# SINTETIZADOR_Y_DDS_SLAVE.net
KiCad netlist of a schematic drawn in Altium Designer
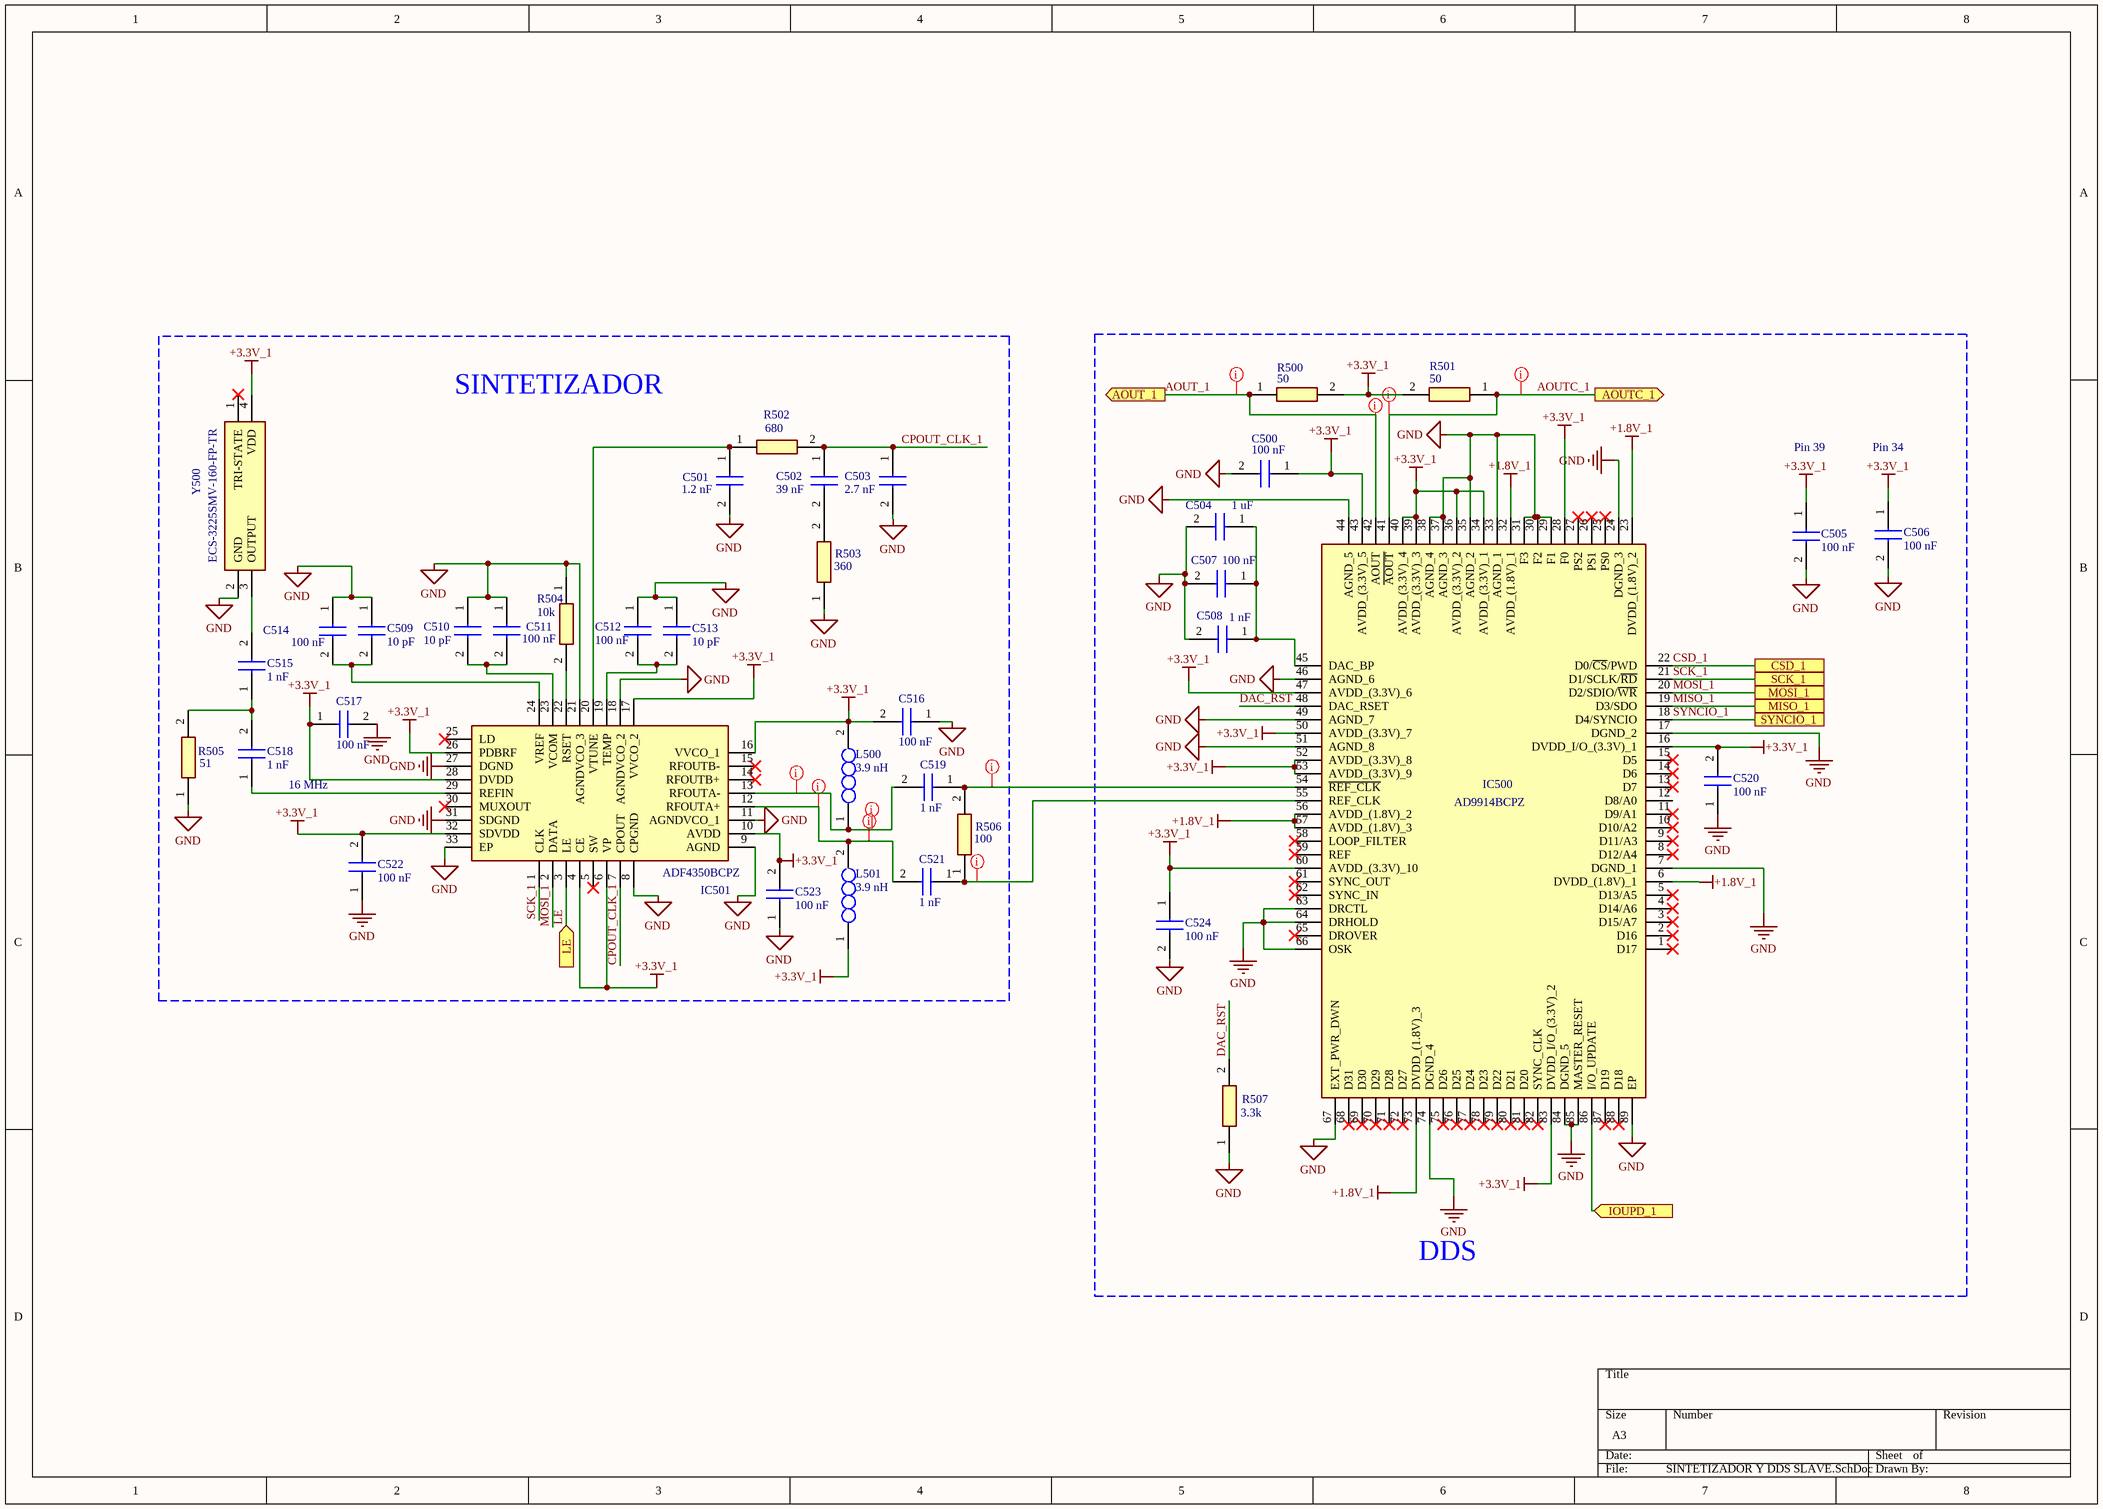
[diagram p0: SINTETIZADOR Y DDS SLAVE.SchDoc]

(export (version "E")
  (design (tool "Eeschema 10.0.6"))
  (components
    (comp (ref "C500")
      (value "100 nF")
      (footprint "SamacSys:C0603")
      (description "Capacitor")
      (fields (field (name "MANUFACTURER_PART_NUMBER") "C0603H470J5GACTU"))
      (libsource (lib "LIBRERIA_GEN_V2.0") (part "C0603H470J5GACTU"))
    )
    (comp (ref "C501")
      (value "1.2 nF")
      (footprint "SamacSys:C0603")
      (description "Capacitor")
      (fields (field (name "MANUFACTURER_PART_NUMBER") "C0603H470J5GACTU"))
      (libsource (lib "LIBRERIA_GEN_V2.0") (part "C0603H470J5GACTU"))
    )
    (comp (ref "C502")
      (value "39 nF")
      (footprint "SamacSys:C0603")
      (description "Capacitor")
      (fields (field (name "MANUFACTURER_PART_NUMBER") "C0603H470J5GACTU"))
      (libsource (lib "LIBRERIA_GEN_V2.0") (part "C0603H470J5GACTU"))
    )
    (comp (ref "C503")
      (value "2.7 nF")
      (footprint "SamacSys:C0603")
      (description "Capacitor")
      (fields (field (name "MANUFACTURER_PART_NUMBER") "C0603H470J5GACTU"))
      (libsource (lib "LIBRERIA_GEN_V2.0") (part "C0603H470J5GACTU"))
    )
    (comp (ref "C504")
      (value "1 uF")
      (footprint "SamacSys:C0603")
      (description "Capacitor")
      (fields (field (name "MANUFACTURER_PART_NUMBER") "C0603H470J5GACTU"))
      (libsource (lib "LIBRERIA_GEN_V2.0") (part "C0603H470J5GACTU"))
    )
    (comp (ref "C505")
      (value "100 nF")
      (footprint "SamacSys:C0603")
      (description "Capacitor")
      (fields (field (name "MANUFACTURER_PART_NUMBER") "C0603H470J5GACTU"))
      (libsource (lib "LIBRERIA_GEN_V2.0") (part "C0603H470J5GACTU"))
    )
    (comp (ref "C506")
      (value "100 nF")
      (footprint "SamacSys:C0603")
      (description "Capacitor")
      (fields (field (name "MANUFACTURER_PART_NUMBER") "C0603H470J5GACTU"))
      (libsource (lib "LIBRERIA_GEN_V2.0") (part "C0603H470J5GACTU"))
    )
    (comp (ref "C507")
      (value "100 nF")
      (footprint "SamacSys:C0603")
      (description "Capacitor")
      (fields (field (name "MANUFACTURER_PART_NUMBER") "C0603H470J5GACTU"))
      (libsource (lib "LIBRERIA_GEN_V2.0") (part "C0603H470J5GACTU"))
    )
    (comp (ref "C508")
      (value "1 nF")
      (footprint "SamacSys:C0603")
      (description "Capacitor")
      (fields (field (name "MANUFACTURER_PART_NUMBER") "C0603H470J5GACTU"))
      (libsource (lib "LIBRERIA_GEN_V2.0") (part "C0603H470J5GACTU"))
    )
    (comp (ref "C509")
      (value "10 pF")
      (footprint "SamacSys:C0603")
      (description "Capacitor")
      (fields (field (name "MANUFACTURER_PART_NUMBER") "C0603H470J5GACTU"))
      (libsource (lib "LIBRERIA_GEN_V2.0") (part "C0603H470J5GACTU"))
    )
    (comp (ref "C510")
      (value "10 pF")
      (footprint "SamacSys:C0603")
      (description "Capacitor")
      (fields (field (name "MANUFACTURER_PART_NUMBER") "C0603H470J5GACTU"))
      (libsource (lib "LIBRERIA_GEN_V2.0") (part "C0603H470J5GACTU"))
    )
    (comp (ref "C511")
      (value "100 nF")
      (footprint "SamacSys:C0603")
      (description "Capacitor")
      (fields (field (name "MANUFACTURER_PART_NUMBER") "C0603H470J5GACTU"))
      (libsource (lib "LIBRERIA_GEN_V2.0") (part "C0603H470J5GACTU"))
    )
    (comp (ref "C512")
      (value "100 nF")
      (footprint "SamacSys:C0603")
      (description "Capacitor")
      (fields (field (name "MANUFACTURER_PART_NUMBER") "C0603H470J5GACTU"))
      (libsource (lib "LIBRERIA_GEN_V2.0") (part "C0603H470J5GACTU"))
    )
    (comp (ref "C513")
      (value "10 pF")
      (footprint "SamacSys:C0603")
      (description "Capacitor")
      (fields (field (name "MANUFACTURER_PART_NUMBER") "C0603H470J5GACTU"))
      (libsource (lib "LIBRERIA_GEN_V2.0") (part "C0603H470J5GACTU"))
    )
    (comp (ref "C514")
      (value "100 nF")
      (footprint "SamacSys:C0603")
      (description "Capacitor")
      (fields (field (name "MANUFACTURER_PART_NUMBER") "C0603H470J5GACTU"))
      (libsource (lib "LIBRERIA_GEN_V2.0") (part "C0603H470J5GACTU"))
    )
    (comp (ref "C515")
      (value "1 nF")
      (footprint "SamacSys:C0603")
      (description "Capacitor")
      (fields (field (name "MANUFACTURER_PART_NUMBER") "C0603H470J5GACTU"))
      (libsource (lib "LIBRERIA_GEN_V2.0") (part "C0603H470J5GACTU"))
    )
    (comp (ref "C516")
      (value "100 nF")
      (footprint "SamacSys:C0603")
      (description "Capacitor")
      (fields (field (name "MANUFACTURER_PART_NUMBER") "C0603H470J5GACTU"))
      (libsource (lib "LIBRERIA_GEN_V2.0") (part "C0603H470J5GACTU"))
    )
    (comp (ref "C517")
      (value "100 nF")
      (footprint "SamacSys:C0603")
      (description "Capacitor")
      (fields (field (name "MANUFACTURER_PART_NUMBER") "C0603H470J5GACTU"))
      (libsource (lib "LIBRERIA_GEN_V2.0") (part "C0603H470J5GACTU"))
    )
    (comp (ref "C518")
      (value "1 nF")
      (footprint "SamacSys:C0603")
      (description "Capacitor")
      (fields (field (name "MANUFACTURER_PART_NUMBER") "C0603H470J5GACTU"))
      (libsource (lib "LIBRERIA_GEN_V2.0") (part "C0603H470J5GACTU"))
    )
    (comp (ref "C519")
      (value "1 nF")
      (footprint "SamacSys:C0603")
      (description "Capacitor")
      (fields (field (name "MANUFACTURER_PART_NUMBER") "C0603H470J5GACTU"))
      (libsource (lib "LIBRERIA_GEN_V2.0") (part "C0603H470J5GACTU"))
    )
    (comp (ref "C520")
      (value "100 nF")
      (footprint "SamacSys:C0603")
      (description "Capacitor")
      (fields (field (name "MANUFACTURER_PART_NUMBER") "C0603H470J5GACTU"))
      (libsource (lib "LIBRERIA_GEN_V2.0") (part "C0603H470J5GACTU"))
    )
    (comp (ref "C521")
      (value "1 nF")
      (footprint "SamacSys:C0603")
      (description "Capacitor")
      (fields (field (name "MANUFACTURER_PART_NUMBER") "C0603H470J5GACTU"))
      (libsource (lib "LIBRERIA_GEN_V2.0") (part "C0603H470J5GACTU"))
    )
    (comp (ref "C522")
      (value "100 nF")
      (footprint "SamacSys:C0603")
      (description "Capacitor")
      (fields (field (name "MANUFACTURER_PART_NUMBER") "C0603H470J5GACTU"))
      (libsource (lib "LIBRERIA_GEN_V2.0") (part "C0603H470J5GACTU"))
    )
    (comp (ref "C523")
      (value "100 nF")
      (footprint "SamacSys:C0603")
      (description "Capacitor")
      (fields (field (name "MANUFACTURER_PART_NUMBER") "C0603H470J5GACTU"))
      (libsource (lib "LIBRERIA_GEN_V2.0") (part "C0603H470J5GACTU"))
    )
    (comp (ref "C524")
      (value "100 nF")
      (footprint "SamacSys:C0603")
      (description "Capacitor")
      (fields (field (name "MANUFACTURER_PART_NUMBER") "C0603H470J5GACTU"))
      (libsource (lib "LIBRERIA_GEN_V2.0") (part "C0603H470J5GACTU"))
    )
    (comp (ref "IC500")
      (value "AD9914BCPZ")
      (footprint "SamacSys:QFN50P1200X1200X90-89N-D")
      (description "Integrated Circuit")
      (fields (field (name "MOUSER PART NUMBER") "584-AD9914BCPZ"))
      (libsource (lib "LIBRERIA_GEN_V2.0") (part "AD9914BCPZ"))
    )
    (comp (ref "IC501")
      (value "ADF4350BCPZ")
      (footprint "SamacSys:QFN50P500X500X100-33N")
      (description "Integrated Circuit")
      (fields (field (name "MOUSER PART NUMBER") "584-ADF4350BCPZ"))
      (libsource (lib "LIBRERIA_GEN_V2.0") (part "ADF4350BCPZ"))
    )
    (comp (ref "L500")
      (value "3.9 nH")
      (footprint "SamacSys:INDC1608X95N")
      (description "Inductor")
      (fields
        (field (name "MANUFACTURER_PART_NUMBER") "AIML-0603-100K-T")
        (field (name "MOUSER PART NUMBER") "815-AIML-0603-100KT")
      )
      (libsource (lib "*") (part "AIML-0603-100K-T"))
    )
    (comp (ref "L501")
      (value "3.9 nH")
      (footprint "SamacSys:INDC1608X95N")
      (description "Inductor")
      (fields
        (field (name "MANUFACTURER_PART_NUMBER") "AIML-0603-100K-T")
        (field (name "MOUSER PART NUMBER") "815-AIML-0603-100KT")
      )
      (libsource (lib "*") (part "AIML-0603-100K-T"))
    )
    (comp (ref "R500")
      (value "50")
      (footprint "SamacSys:RESC1608X55N")
      (description "Resistor")
      (fields
        (field (name "MANUFACTURER_PART_NUMBER") "CR0603-FX-1431ELF")
        (field (name "MOUSER PART NUMBER") "652-CR0603FX-1431ELF")
      )
      (libsource (lib "") (part "CR0603-FX-1431ELF_1"))
    )
    (comp (ref "R501")
      (value "50")
      (footprint "SamacSys:RESC1608X55N")
      (description "Resistor")
      (fields
        (field (name "MANUFACTURER_PART_NUMBER") "CR0603-FX-1431ELF")
        (field (name "MOUSER PART NUMBER") "652-CR0603FX-1431ELF")
      )
      (libsource (lib "") (part "CR0603-FX-1431ELF_2"))
    )
    (comp (ref "R502")
      (value "680")
      (footprint "SamacSys:RESC1608X55N")
      (description "Resistor")
      (fields
        (field (name "MANUFACTURER_PART_NUMBER") "CR0603-FX-1431ELF")
        (field (name "MOUSER PART NUMBER") "652-CR0603FX-1431ELF")
      )
      (libsource (lib "") (part "CR0603-FX-1431ELF_1"))
    )
    (comp (ref "R503")
      (value "360")
      (footprint "SamacSys:RESC1608X55N")
      (description "Resistor")
      (fields
        (field (name "MANUFACTURER_PART_NUMBER") "CR0603-FX-1431ELF")
        (field (name "MOUSER PART NUMBER") "652-CR0603FX-1431ELF")
      )
      (libsource (lib "") (part "CR0603-FX-1431ELF_3"))
    )
    (comp (ref "R504")
      (value "10k")
      (footprint "SamacSys:RESC1608X55N")
      (description "Resistor")
      (fields
        (field (name "MANUFACTURER_PART_NUMBER") "CR0603-FX-1431ELF")
        (field (name "MOUSER PART NUMBER") "652-CR0603FX-1431ELF")
      )
      (libsource (lib "LIBRERIA_GEN_V2.0") (part "CR0603-FX-1431ELF"))
    )
    (comp (ref "R505")
      (value "51")
      (footprint "SamacSys:RESC1608X55N")
      (description "Resistor")
      (fields
        (field (name "MANUFACTURER_PART_NUMBER") "CR0603-FX-1431ELF")
        (field (name "MOUSER PART NUMBER") "652-CR0603FX-1431ELF")
      )
      (libsource (lib "") (part "CR0603-FX-1431ELF_3"))
    )
    (comp (ref "R506")
      (value "100")
      (footprint "SamacSys:RESC1608X55N")
      (description "Resistor")
      (fields
        (field (name "MANUFACTURER_PART_NUMBER") "CR0603-FX-1431ELF")
        (field (name "MOUSER PART NUMBER") "652-CR0603FX-1431ELF")
      )
      (libsource (lib "") (part "CR0603-FX-1431ELF_3"))
    )
    (comp (ref "R507")
      (value "3.3k")
      (footprint "SamacSys:RESC1608X55N")
      (description "Resistor")
      (fields
        (field (name "MANUFACTURER_PART_NUMBER") "CR0603-FX-1431ELF")
        (field (name "MOUSER PART NUMBER") "652-CR0603FX-1431ELF")
      )
      (libsource (lib "") (part "CR0603-FX-1431ELF_3"))
    )
    (comp (ref "Y500")
      (value "ECS-3225SMV-160-FP-TR")
      (footprint "SamacSys:ECS3225SMV160FPTR")
      (description "Crystal or Oscillator")
      (fields (field (name "MOUSER PART NUMBER") "520-3225SMV-160-FPT"))
      (libsource (lib "LIBRERIA_GEN_V2.0") (part "ECS-3225SMV-160-FP-TR"))
    )
  )
  (nets
    (net (code "1") (name "+1.8V_1") (class "Default")
      (node (ref "IC500") (pin "23") (pinfunction "DVDD_(1.8V)_2_23") (pintype "passive"))
      (node (ref "IC500") (pin "32") (pinfunction "AVDD_(1.8V)_1_32") (pintype "passive"))
      (node (ref "IC500") (pin "56") (pinfunction "AVDD_(1.8V)_2_56") (pintype "passive"))
      (node (ref "IC500") (pin "57") (pinfunction "AVDD_(1.8V)_3_57") (pintype "passive"))
      (node (ref "IC500") (pin "6") (pinfunction "DVDD_(1.8V)_1_6") (pintype "passive"))
      (node (ref "IC500") (pin "73") (pinfunction "DVDD_(1.8V)_3_73") (pintype "passive"))
    )
    (net (code "2") (name "+3.3V_1") (class "Default")
      (node (ref "C500") (pin "1") (pinfunction "1_1") (pintype "passive"))
      (node (ref "C505") (pin "1") (pinfunction "1_1") (pintype "passive"))
      (node (ref "C506") (pin "1") (pinfunction "1_1") (pintype "passive"))
      (node (ref "C516") (pin "2") (pinfunction "2_2") (pintype "passive"))
      (node (ref "C517") (pin "1") (pinfunction "1_1") (pintype "passive"))
      (node (ref "C520") (pin "2") (pinfunction "2_2") (pintype "passive"))
      (node (ref "C522") (pin "2") (pinfunction "2_2") (pintype "passive"))
      (node (ref "C523") (pin "2") (pinfunction "2_2") (pintype "passive"))
      (node (ref "C524") (pin "1") (pinfunction "1_1") (pintype "passive"))
      (node (ref "IC500") (pin "16") (pinfunction "DVDD_I/O_(3.3V)_1_16") (pintype "passive"))
      (node (ref "IC500") (pin "28") (pinfunction "F0_28") (pintype "passive"))
      (node (ref "IC500") (pin "34") (pinfunction "AVDD_(3.3V)_1_34") (pintype "passive"))
      (node (ref "IC500") (pin "36") (pinfunction "AVDD_(3.3V)_2_36") (pintype "passive"))
      (node (ref "IC500") (pin "39") (pinfunction "AVDD_(3.3V)_3_39") (pintype "passive"))
      (node (ref "IC500") (pin "40") (pinfunction "AVDD_(3.3V)_4_40") (pintype "passive"))
      (node (ref "IC500") (pin "43") (pinfunction "AVDD_(3.3V)_5_43") (pintype "passive"))
      (node (ref "IC500") (pin "47") (pinfunction "AVDD_(3.3V)_6_47") (pintype "passive"))
      (node (ref "IC500") (pin "50") (pinfunction "AVDD_(3.3V)_7_50") (pintype "passive"))
      (node (ref "IC500") (pin "52") (pinfunction "AVDD_(3.3V)_8_52") (pintype "passive"))
      (node (ref "IC500") (pin "53") (pinfunction "AVDD_(3.3V)_9_53") (pintype "passive"))
      (node (ref "IC500") (pin "60") (pinfunction "AVDD_(3.3V)_10_60") (pintype "passive"))
      (node (ref "IC500") (pin "83") (pinfunction "DVDD_I/O_(3.3V)_2_83") (pintype "passive"))
      (node (ref "IC501") (pin "10") (pinfunction "AVDD_10") (pintype "passive"))
      (node (ref "IC501") (pin "16") (pinfunction "VVCO_1_16") (pintype "passive"))
      (node (ref "IC501") (pin "17") (pinfunction "VVCO_2_17") (pintype "passive"))
      (node (ref "IC501") (pin "26") (pinfunction "PDBRF_26") (pintype "passive"))
      (node (ref "IC501") (pin "28") (pinfunction "DVDD_28") (pintype "passive"))
      (node (ref "IC501") (pin "32") (pinfunction "SDVDD_32") (pintype "passive"))
      (node (ref "IC501") (pin "4") (pinfunction "CE_4") (pintype "passive"))
      (node (ref "IC501") (pin "6") (pinfunction "VP_6") (pintype "passive"))
      (node (ref "L500") (pin "2") (pinfunction "2_2") (pintype "passive"))
      (node (ref "L501") (pin "1") (pinfunction "1_1") (pintype "passive"))
      (node (ref "R500") (pin "2") (pinfunction "2_2") (pintype "passive"))
      (node (ref "R501") (pin "2") (pinfunction "2_2") (pintype "passive"))
      (node (ref "Y500") (pin "4") (pinfunction "VDD_4") (pintype "passive"))
    )
    (net (code "3") (name "/AOUTC_1") (class "Default")
      (node (ref "IC500") (pin "41") (pinfunction "~{AOUT}_41") (pintype "passive"))
      (node (ref "R501") (pin "1") (pinfunction "1_1") (pintype "passive"))
    )
    (net (code "4") (name "/AOUT_1") (class "Default")
      (node (ref "IC500") (pin "42") (pinfunction "AOUT_42") (pintype "passive"))
      (node (ref "R500") (pin "1") (pinfunction "1_1") (pintype "passive"))
    )
    (net (code "5") (name "/CPOUT_CLK_1") (class "Default")
      (node (ref "C502") (pin "1") (pinfunction "1_1") (pintype "passive"))
      (node (ref "C503") (pin "1") (pinfunction "1_1") (pintype "passive"))
      (node (ref "IC501") (pin "7") (pinfunction "CPOUT_7") (pintype "passive"))
      (node (ref "R502") (pin "2") (pinfunction "2_2") (pintype "passive"))
    )
    (net (code "6") (name "/CSD_1") (class "Default")
      (node (ref "IC500") (pin "22") (pinfunction "D0/~{CS}/PWD_22") (pintype "passive"))
    )
    (net (code "7") (name "/DAC_RST") (class "Default")
      (node (ref "IC500") (pin "48") (pinfunction "DAC_RSET_48") (pintype "passive"))
      (node (ref "R507") (pin "2") (pinfunction "2_2") (pintype "passive"))
    )
    (net (code "8") (name "/IOUPD_1") (class "Default")
      (node (ref "IC500") (pin "86") (pinfunction "I/O_UPDATE_86") (pintype "passive"))
    )
    (net (code "9") (name "/LE") (class "Default")
      (node (ref "IC501") (pin "3") (pinfunction "LE_3") (pintype "passive"))
    )
    (net (code "10") (name "/MISO_1") (class "Default")
      (node (ref "IC500") (pin "19") (pinfunction "D3/SDO_19") (pintype "passive"))
    )
    (net (code "11") (name "/MOSI_1") (class "Default")
      (node (ref "IC500") (pin "20") (pinfunction "D2/SDIO/~{WR}_20") (pintype "passive"))
      (node (ref "IC501") (pin "2") (pinfunction "DATA_2") (pintype "passive"))
    )
    (net (code "12") (name "/SCK_1") (class "Default")
      (node (ref "IC500") (pin "21") (pinfunction "D1/SCLK/~{RD}_21") (pintype "passive"))
      (node (ref "IC501") (pin "1") (pinfunction "CLK_1") (pintype "passive"))
    )
    (net (code "13") (name "/SYNCIO_1") (class "Default")
      (node (ref "IC500") (pin "18") (pinfunction "D4/SYNCIO_18") (pintype "passive"))
    )
    (net (code "14") (name "GND") (class "Default")
      (node (ref "C500") (pin "2") (pinfunction "2_2") (pintype "passive"))
      (node (ref "C501") (pin "2") (pinfunction "2_2") (pintype "passive"))
      (node (ref "C503") (pin "2") (pinfunction "2_2") (pintype "passive"))
      (node (ref "C504") (pin "2") (pinfunction "2_2") (pintype "passive"))
      (node (ref "C505") (pin "2") (pinfunction "2_2") (pintype "passive"))
      (node (ref "C506") (pin "2") (pinfunction "2_2") (pintype "passive"))
      (node (ref "C507") (pin "2") (pinfunction "2_2") (pintype "passive"))
      (node (ref "C508") (pin "2") (pinfunction "2_2") (pintype "passive"))
      (node (ref "C509") (pin "1") (pinfunction "1_1") (pintype "passive"))
      (node (ref "C510") (pin "1") (pinfunction "1_1") (pintype "passive"))
      (node (ref "C511") (pin "1") (pinfunction "1_1") (pintype "passive"))
      (node (ref "C512") (pin "1") (pinfunction "1_1") (pintype "passive"))
      (node (ref "C513") (pin "1") (pinfunction "1_1") (pintype "passive"))
      (node (ref "C514") (pin "1") (pinfunction "1_1") (pintype "passive"))
      (node (ref "C516") (pin "1") (pinfunction "1_1") (pintype "passive"))
      (node (ref "C517") (pin "2") (pinfunction "2_2") (pintype "passive"))
      (node (ref "C520") (pin "1") (pinfunction "1_1") (pintype "passive"))
      (node (ref "C522") (pin "1") (pinfunction "1_1") (pintype "passive"))
      (node (ref "C523") (pin "1") (pinfunction "1_1") (pintype "passive"))
      (node (ref "C524") (pin "2") (pinfunction "2_2") (pintype "passive"))
      (node (ref "IC500") (pin "17") (pinfunction "DGND_2_17") (pintype "passive"))
      (node (ref "IC500") (pin "24") (pinfunction "DGND_3_24") (pintype "passive"))
      (node (ref "IC500") (pin "29") (pinfunction "F1_29") (pintype "passive"))
      (node (ref "IC500") (pin "30") (pinfunction "F2_30") (pintype "passive"))
      (node (ref "IC500") (pin "31") (pinfunction "F3_31") (pintype "passive"))
      (node (ref "IC500") (pin "33") (pinfunction "AGND_1_33") (pintype "passive"))
      (node (ref "IC500") (pin "35") (pinfunction "AGND_2_35") (pintype "passive"))
      (node (ref "IC500") (pin "37") (pinfunction "AGND_3_37") (pintype "passive"))
      (node (ref "IC500") (pin "38") (pinfunction "AGND_4_38") (pintype "passive"))
      (node (ref "IC500") (pin "44") (pinfunction "AGND_5_44") (pintype "passive"))
      (node (ref "IC500") (pin "46") (pinfunction "AGND_6_46") (pintype "passive"))
      (node (ref "IC500") (pin "49") (pinfunction "AGND_7_49") (pintype "passive"))
      (node (ref "IC500") (pin "51") (pinfunction "AGND_8_51") (pintype "passive"))
      (node (ref "IC500") (pin "63") (pinfunction "DRCTL_63") (pintype "passive"))
      (node (ref "IC500") (pin "64") (pinfunction "DRHOLD_64") (pintype "passive"))
      (node (ref "IC500") (pin "66") (pinfunction "OSK_66") (pintype "passive"))
      (node (ref "IC500") (pin "67") (pinfunction "EXT_PWR_DWN_67") (pintype "passive"))
      (node (ref "IC500") (pin "7") (pinfunction "DGND_1_7") (pintype "passive"))
      (node (ref "IC500") (pin "74") (pinfunction "DGND_4_74") (pintype "passive"))
      (node (ref "IC500") (pin "84") (pinfunction "DGND_5_84") (pintype "passive"))
      (node (ref "IC500") (pin "85") (pinfunction "MASTER_RESET_85") (pintype "passive"))
      (node (ref "IC500") (pin "89") (pinfunction "EP_89") (pintype "passive"))
      (node (ref "IC501") (pin "11") (pinfunction "AGNDVCO_1_11") (pintype "passive"))
      (node (ref "IC501") (pin "18") (pinfunction "AGNDVCO_2_18") (pintype "passive"))
      (node (ref "IC501") (pin "21") (pinfunction "AGNDVCO_3_21") (pintype "passive"))
      (node (ref "IC501") (pin "27") (pinfunction "DGND_27") (pintype "passive"))
      (node (ref "IC501") (pin "31") (pinfunction "SDGND_31") (pintype "passive"))
      (node (ref "IC501") (pin "33") (pinfunction "EP_33") (pintype "passive"))
      (node (ref "IC501") (pin "8") (pinfunction "CPGND_8") (pintype "passive"))
      (node (ref "IC501") (pin "9") (pinfunction "AGND_9") (pintype "passive"))
      (node (ref "R503") (pin "1") (pinfunction "1_1") (pintype "passive"))
      (node (ref "R504") (pin "1") (pinfunction "1_1") (pintype "passive"))
      (node (ref "R505") (pin "1") (pinfunction "1_1") (pintype "passive"))
      (node (ref "R507") (pin "1") (pinfunction "1_1") (pintype "passive"))
      (node (ref "Y500") (pin "2") (pinfunction "GND_2") (pintype "passive"))
    )
    (net (code "15") (name "Net-(C502-Pad2)") (class "Default")
      (node (ref "C502") (pin "2") (pinfunction "2_2") (pintype "passive"))
      (node (ref "R503") (pin "2") (pinfunction "2_2") (pintype "passive"))
    )
    (net (code "16") (name "Net-(C515-Pad1)") (class "Default")
      (node (ref "C515") (pin "1") (pinfunction "1_1") (pintype "passive"))
      (node (ref "C518") (pin "2") (pinfunction "2_2") (pintype "passive"))
      (node (ref "R505") (pin "2") (pinfunction "2_2") (pintype "passive"))
    )
    (net (code "17") (name "Net-(IC500-DAC_BP)") (class "Default")
      (node (ref "C504") (pin "1") (pinfunction "1_1") (pintype "passive"))
      (node (ref "C507") (pin "1") (pinfunction "1_1") (pintype "passive"))
      (node (ref "C508") (pin "1") (pinfunction "1_1") (pintype "passive"))
      (node (ref "IC500") (pin "45") (pinfunction "DAC_BP_45") (pintype "passive"))
    )
    (net (code "18") (name "Net-(IC500-REF_CLK)") (class "Default")
      (node (ref "C521") (pin "1") (pinfunction "1_1") (pintype "passive"))
      (node (ref "IC500") (pin "55") (pinfunction "REF_CLK_55") (pintype "passive"))
      (node (ref "R506") (pin "1") (pinfunction "1_1") (pintype "passive"))
    )
    (net (code "19") (name "Net-(IC500-~{REF_CLK})") (class "Default")
      (node (ref "C519") (pin "1") (pinfunction "1_1") (pintype "passive"))
      (node (ref "IC500") (pin "54") (pinfunction "~{REF_CLK}_54") (pintype "passive"))
      (node (ref "R506") (pin "2") (pinfunction "2_2") (pintype "passive"))
    )
    (net (code "20") (name "Net-(IC501-REFIN)") (class "Default")
      (node (ref "C518") (pin "1") (pinfunction "1_1") (pintype "passive"))
      (node (ref "IC501") (pin "29") (pinfunction "REFIN_29") (pintype "passive"))
    )
    (net (code "21") (name "Net-(IC501-RFOUTA+)") (class "Default")
      (node (ref "C521") (pin "2") (pinfunction "2_2") (pintype "passive"))
      (node (ref "IC501") (pin "12") (pinfunction "RFOUTA+_12") (pintype "passive"))
      (node (ref "L501") (pin "2") (pinfunction "2_2") (pintype "passive"))
    )
    (net (code "22") (name "Net-(IC501-RFOUTA-)") (class "Default")
      (node (ref "C519") (pin "2") (pinfunction "2_2") (pintype "passive"))
      (node (ref "IC501") (pin "13") (pinfunction "RFOUTA-_13") (pintype "passive"))
      (node (ref "L500") (pin "1") (pinfunction "1_1") (pintype "passive"))
    )
    (net (code "23") (name "Net-(IC501-RSET)") (class "Default")
      (node (ref "IC501") (pin "22") (pinfunction "RSET_22") (pintype "passive"))
      (node (ref "R504") (pin "2") (pinfunction "2_2") (pintype "passive"))
    )
    (net (code "24") (name "Net-(IC501-TEMP)") (class "Default")
      (node (ref "C512") (pin "2") (pinfunction "2_2") (pintype "passive"))
      (node (ref "C513") (pin "2") (pinfunction "2_2") (pintype "passive"))
      (node (ref "IC501") (pin "19") (pinfunction "TEMP_19") (pintype "passive"))
    )
    (net (code "25") (name "Net-(IC501-VCOM)") (class "Default")
      (node (ref "C510") (pin "2") (pinfunction "2_2") (pintype "passive"))
      (node (ref "C511") (pin "2") (pinfunction "2_2") (pintype "passive"))
      (node (ref "IC501") (pin "23") (pinfunction "VCOM_23") (pintype "passive"))
    )
    (net (code "26") (name "Net-(IC501-VREF)") (class "Default")
      (node (ref "C509") (pin "2") (pinfunction "2_2") (pintype "passive"))
      (node (ref "C514") (pin "2") (pinfunction "2_2") (pintype "passive"))
      (node (ref "IC501") (pin "24") (pinfunction "VREF_24") (pintype "passive"))
    )
    (net (code "27") (name "Net-(IC501-VTUNE)") (class "Default")
      (node (ref "C501") (pin "1") (pinfunction "1_1") (pintype "passive"))
      (node (ref "IC501") (pin "20") (pinfunction "VTUNE_20") (pintype "passive"))
      (node (ref "R502") (pin "1") (pinfunction "1_1") (pintype "passive"))
    )
    (net (code "28") (name "Net-(Y500-OUTPUT)") (class "Default")
      (node (ref "C515") (pin "2") (pinfunction "2_2") (pintype "passive"))
      (node (ref "Y500") (pin "3") (pinfunction "OUTPUT_3") (pintype "passive"))
    )
    (net (code "29") (name "unconnected-(IC500-D5-Pad15)") (class "Default")
      (node (ref "IC500") (pin "15") (pinfunction "D5_15") (pintype "passive+no_connect"))
    )
    (net (code "30") (name "unconnected-(IC500-D6-Pad14)") (class "Default")
      (node (ref "IC500") (pin "14") (pinfunction "D6_14") (pintype "passive+no_connect"))
    )
    (net (code "31") (name "unconnected-(IC500-D7-Pad13)") (class "Default")
      (node (ref "IC500") (pin "13") (pinfunction "D7_13") (pintype "passive+no_connect"))
    )
    (net (code "32") (name "unconnected-(IC500-D8{slash}A0-Pad12)") (class "Default")
      (node (ref "IC500") (pin "12") (pinfunction "D8/A0_12") (pintype "passive"))
    )
    (net (code "33") (name "unconnected-(IC500-D9{slash}A1-Pad11)") (class "Default")
      (node (ref "IC500") (pin "11") (pinfunction "D9/A1_11") (pintype "passive+no_connect"))
    )
    (net (code "34") (name "unconnected-(IC500-D10{slash}A2-Pad10)") (class "Default")
      (node (ref "IC500") (pin "10") (pinfunction "D10/A2_10") (pintype "passive+no_connect"))
    )
    (net (code "35") (name "unconnected-(IC500-D11{slash}A3-Pad9)") (class "Default")
      (node (ref "IC500") (pin "9") (pinfunction "D11/A3_9") (pintype "passive+no_connect"))
    )
    (net (code "36") (name "unconnected-(IC500-D12{slash}A4-Pad8)") (class "Default")
      (node (ref "IC500") (pin "8") (pinfunction "D12/A4_8") (pintype "passive+no_connect"))
    )
    (net (code "37") (name "unconnected-(IC500-D13{slash}A5-Pad5)") (class "Default")
      (node (ref "IC500") (pin "5") (pinfunction "D13/A5_5") (pintype "passive+no_connect"))
    )
    (net (code "38") (name "unconnected-(IC500-D14{slash}A6-Pad4)") (class "Default")
      (node (ref "IC500") (pin "4") (pinfunction "D14/A6_4") (pintype "passive+no_connect"))
    )
    (net (code "39") (name "unconnected-(IC500-D15{slash}A7-Pad3)") (class "Default")
      (node (ref "IC500") (pin "3") (pinfunction "D15/A7_3") (pintype "passive+no_connect"))
    )
    (net (code "40") (name "unconnected-(IC500-D16-Pad2)") (class "Default")
      (node (ref "IC500") (pin "2") (pinfunction "D16_2") (pintype "passive+no_connect"))
    )
    (net (code "41") (name "unconnected-(IC500-D17-Pad1)") (class "Default")
      (node (ref "IC500") (pin "1") (pinfunction "D17_1") (pintype "passive+no_connect"))
    )
    (net (code "42") (name "unconnected-(IC500-D18-Pad88)") (class "Default")
      (node (ref "IC500") (pin "88") (pinfunction "D18_88") (pintype "passive+no_connect"))
    )
    (net (code "43") (name "unconnected-(IC500-D19-Pad87)") (class "Default")
      (node (ref "IC500") (pin "87") (pinfunction "D19_87") (pintype "passive+no_connect"))
    )
    (net (code "44") (name "unconnected-(IC500-D20-Pad81)") (class "Default")
      (node (ref "IC500") (pin "81") (pinfunction "D20_81") (pintype "passive+no_connect"))
    )
    (net (code "45") (name "unconnected-(IC500-D21-Pad80)") (class "Default")
      (node (ref "IC500") (pin "80") (pinfunction "D21_80") (pintype "passive+no_connect"))
    )
    (net (code "46") (name "unconnected-(IC500-D22-Pad79)") (class "Default")
      (node (ref "IC500") (pin "79") (pinfunction "D22_79") (pintype "passive+no_connect"))
    )
    (net (code "47") (name "unconnected-(IC500-D23-Pad78)") (class "Default")
      (node (ref "IC500") (pin "78") (pinfunction "D23_78") (pintype "passive+no_connect"))
    )
    (net (code "48") (name "unconnected-(IC500-D24-Pad77)") (class "Default")
      (node (ref "IC500") (pin "77") (pinfunction "D24_77") (pintype "passive+no_connect"))
    )
    (net (code "49") (name "unconnected-(IC500-D25-Pad76)") (class "Default")
      (node (ref "IC500") (pin "76") (pinfunction "D25_76") (pintype "passive+no_connect"))
    )
    (net (code "50") (name "unconnected-(IC500-D26-Pad75)") (class "Default")
      (node (ref "IC500") (pin "75") (pinfunction "D26_75") (pintype "passive+no_connect"))
    )
    (net (code "51") (name "unconnected-(IC500-D27-Pad72)") (class "Default")
      (node (ref "IC500") (pin "72") (pinfunction "D27_72") (pintype "passive+no_connect"))
    )
    (net (code "52") (name "unconnected-(IC500-D28-Pad71)") (class "Default")
      (node (ref "IC500") (pin "71") (pinfunction "D28_71") (pintype "passive+no_connect"))
    )
    (net (code "53") (name "unconnected-(IC500-D29-Pad70)") (class "Default")
      (node (ref "IC500") (pin "70") (pinfunction "D29_70") (pintype "passive+no_connect"))
    )
    (net (code "54") (name "unconnected-(IC500-D30-Pad69)") (class "Default")
      (node (ref "IC500") (pin "69") (pinfunction "D30_69") (pintype "passive+no_connect"))
    )
    (net (code "55") (name "unconnected-(IC500-D31-Pad68)") (class "Default")
      (node (ref "IC500") (pin "68") (pinfunction "D31_68") (pintype "passive+no_connect"))
    )
    (net (code "56") (name "unconnected-(IC500-DROVER-Pad65)") (class "Default")
      (node (ref "IC500") (pin "65") (pinfunction "DROVER_65") (pintype "passive+no_connect"))
    )
    (net (code "57") (name "unconnected-(IC500-LOOP_FILTER-Pad58)") (class "Default")
      (node (ref "IC500") (pin "58") (pinfunction "LOOP_FILTER_58") (pintype "passive+no_connect"))
    )
    (net (code "58") (name "unconnected-(IC500-PS0-Pad25)") (class "Default")
      (node (ref "IC500") (pin "25") (pinfunction "PS0_25") (pintype "passive+no_connect"))
    )
    (net (code "59") (name "unconnected-(IC500-PS1-Pad26)") (class "Default")
      (node (ref "IC500") (pin "26") (pinfunction "PS1_26") (pintype "passive+no_connect"))
    )
    (net (code "60") (name "unconnected-(IC500-PS2-Pad27)") (class "Default")
      (node (ref "IC500") (pin "27") (pinfunction "PS2_27") (pintype "passive+no_connect"))
    )
    (net (code "61") (name "unconnected-(IC500-REF-Pad59)") (class "Default")
      (node (ref "IC500") (pin "59") (pinfunction "REF_59") (pintype "passive+no_connect"))
    )
    (net (code "62") (name "unconnected-(IC500-SYNC_CLK-Pad82)") (class "Default")
      (node (ref "IC500") (pin "82") (pinfunction "SYNC_CLK_82") (pintype "passive+no_connect"))
    )
    (net (code "63") (name "unconnected-(IC500-SYNC_IN-Pad62)") (class "Default")
      (node (ref "IC500") (pin "62") (pinfunction "SYNC_IN_62") (pintype "passive+no_connect"))
    )
    (net (code "64") (name "unconnected-(IC500-SYNC_OUT-Pad61)") (class "Default")
      (node (ref "IC500") (pin "61") (pinfunction "SYNC_OUT_61") (pintype "passive+no_connect"))
    )
    (net (code "65") (name "unconnected-(IC501-LD-Pad25)") (class "Default")
      (node (ref "IC501") (pin "25") (pinfunction "LD_25") (pintype "passive+no_connect"))
    )
    (net (code "66") (name "unconnected-(IC501-MUXOUT-Pad30)") (class "Default")
      (node (ref "IC501") (pin "30") (pinfunction "MUXOUT_30") (pintype "passive+no_connect"))
    )
    (net (code "67") (name "unconnected-(IC501-RFOUTB+-Pad14)") (class "Default")
      (node (ref "IC501") (pin "14") (pinfunction "RFOUTB+_14") (pintype "passive+no_connect"))
    )
    (net (code "68") (name "unconnected-(IC501-RFOUTB--Pad15)") (class "Default")
      (node (ref "IC501") (pin "15") (pinfunction "RFOUTB-_15") (pintype "passive+no_connect"))
    )
    (net (code "69") (name "unconnected-(IC501-SW-Pad5)") (class "Default")
      (node (ref "IC501") (pin "5") (pinfunction "SW_5") (pintype "passive+no_connect"))
    )
    (net (code "70") (name "unconnected-(Y500-TRI-STATE-Pad1)") (class "Default")
      (node (ref "Y500") (pin "1") (pinfunction "TRI-STATE_1") (pintype "passive+no_connect"))
    )
  )
)
